# Rx.net
KiCad netlist of a schematic drawn in EAGLE
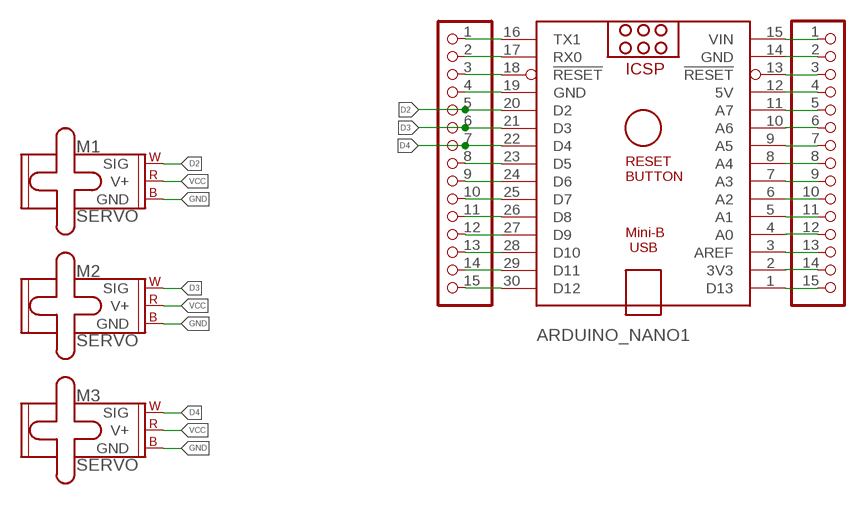
[diagram p0: schematic, sheet 1]

(export (version "E")
  (design (tool "Eeschema 10.0.6"))
  (components
    (comp (ref "ARDUINO_NANO1")
      (value "ARDUINO_NANO")
      (footprint "eagle-import:ARDUINO_NANO")
      (libsource (lib "eagle-import") (part "ARDUINO_NANO"))
    )
    (comp (ref "JP1")
      (value "PINHD-1X15-CB")
      (footprint "eagle-import:1X15-CB")
      (libsource (lib "eagle-import") (part "PINHD-1X15-CB"))
    )
    (comp (ref "JP2")
      (value "PINHD-1X15-CB")
      (footprint "eagle-import:1X15-CB")
      (libsource (lib "eagle-import") (part "PINHD-1X15-CB"))
    )
    (comp (ref "M1")
      (value "SERVO")
      (footprint "eagle-import:1X03")
      (libsource (lib "eagle-import") (part "SERVO"))
    )
    (comp (ref "M2")
      (value "SERVO")
      (footprint "eagle-import:1X03")
      (libsource (lib "eagle-import") (part "SERVO"))
    )
    (comp (ref "M3")
      (value "SERVO")
      (footprint "eagle-import:1X03")
      (libsource (lib "eagle-import") (part "SERVO"))
    )
  )
  (nets
    (net (code "1") (name "D2") (class "Default")
      (node (ref "ARDUINO_NANO1") (pin "20") (pinfunction "D2_20") (pintype "bidirectional"))
      (node (ref "JP2") (pin "5") (pinfunction "5_5") (pintype "passive"))
      (node (ref "M1") (pin "1") (pinfunction "SIG_1") (pintype "bidirectional"))
    )
    (net (code "2") (name "D3") (class "Default")
      (node (ref "ARDUINO_NANO1") (pin "21") (pinfunction "D3_21") (pintype "bidirectional"))
      (node (ref "JP2") (pin "6") (pinfunction "6_6") (pintype "passive"))
      (node (ref "M2") (pin "1") (pinfunction "SIG_1") (pintype "bidirectional"))
    )
    (net (code "3") (name "D4") (class "Default")
      (node (ref "ARDUINO_NANO1") (pin "22") (pinfunction "D4_22") (pintype "bidirectional"))
      (node (ref "JP2") (pin "7") (pinfunction "7_7") (pintype "passive"))
      (node (ref "M3") (pin "1") (pinfunction "SIG_1") (pintype "bidirectional"))
    )
    (net (code "4") (name "GND") (class "Default")
      (node (ref "M1") (pin "3") (pinfunction "GND_3") (pintype "bidirectional"))
      (node (ref "M2") (pin "3") (pinfunction "GND_3") (pintype "bidirectional"))
      (node (ref "M3") (pin "3") (pinfunction "GND_3") (pintype "bidirectional"))
    )
    (net (code "5") (name "Net-(ARDUINO_NANO1-3V3)") (class "Default")
      (node (ref "ARDUINO_NANO1") (pin "2") (pinfunction "3V3_2") (pintype "output"))
      (node (ref "JP1") (pin "14") (pinfunction "14_14") (pintype "passive"))
    )
    (net (code "6") (name "Net-(ARDUINO_NANO1-5V)") (class "Default")
      (node (ref "ARDUINO_NANO1") (pin "12") (pinfunction "5V_12") (pintype "power_in"))
      (node (ref "JP1") (pin "4") (pinfunction "4_4") (pintype "passive"))
    )
    (net (code "7") (name "Net-(ARDUINO_NANO1-A0)") (class "Default")
      (node (ref "ARDUINO_NANO1") (pin "4") (pinfunction "A0_4") (pintype "bidirectional"))
      (node (ref "JP1") (pin "12") (pinfunction "12_12") (pintype "passive"))
    )
    (net (code "8") (name "Net-(ARDUINO_NANO1-A1)") (class "Default")
      (node (ref "ARDUINO_NANO1") (pin "5") (pinfunction "A1_5") (pintype "bidirectional"))
      (node (ref "JP1") (pin "11") (pinfunction "11_11") (pintype "passive"))
    )
    (net (code "9") (name "Net-(ARDUINO_NANO1-A2)") (class "Default")
      (node (ref "ARDUINO_NANO1") (pin "6") (pinfunction "A2_6") (pintype "bidirectional"))
      (node (ref "JP1") (pin "10") (pinfunction "10_10") (pintype "passive"))
    )
    (net (code "10") (name "Net-(ARDUINO_NANO1-A3)") (class "Default")
      (node (ref "ARDUINO_NANO1") (pin "7") (pinfunction "A3_7") (pintype "bidirectional"))
      (node (ref "JP1") (pin "9") (pinfunction "9_9") (pintype "passive"))
    )
    (net (code "11") (name "Net-(ARDUINO_NANO1-A4)") (class "Default")
      (node (ref "ARDUINO_NANO1") (pin "8") (pinfunction "A4_8") (pintype "bidirectional"))
      (node (ref "JP1") (pin "8") (pinfunction "8_8") (pintype "passive"))
    )
    (net (code "12") (name "Net-(ARDUINO_NANO1-A5)") (class "Default")
      (node (ref "ARDUINO_NANO1") (pin "9") (pinfunction "A5_9") (pintype "bidirectional"))
      (node (ref "JP1") (pin "7") (pinfunction "7_7") (pintype "passive"))
    )
    (net (code "13") (name "Net-(ARDUINO_NANO1-A6)") (class "Default")
      (node (ref "ARDUINO_NANO1") (pin "10") (pinfunction "A6_10") (pintype "bidirectional"))
      (node (ref "JP1") (pin "6") (pinfunction "6_6") (pintype "passive"))
    )
    (net (code "14") (name "Net-(ARDUINO_NANO1-A7)") (class "Default")
      (node (ref "ARDUINO_NANO1") (pin "11") (pinfunction "A7_11") (pintype "bidirectional"))
      (node (ref "JP1") (pin "5") (pinfunction "5_5") (pintype "passive"))
    )
    (net (code "15") (name "Net-(ARDUINO_NANO1-AREF)") (class "Default")
      (node (ref "ARDUINO_NANO1") (pin "3") (pinfunction "AREF_3") (pintype "input"))
      (node (ref "JP1") (pin "13") (pinfunction "13_13") (pintype "passive"))
    )
    (net (code "16") (name "Net-(ARDUINO_NANO1-D5)") (class "Default")
      (node (ref "ARDUINO_NANO1") (pin "23") (pinfunction "D5_23") (pintype "bidirectional"))
      (node (ref "JP2") (pin "8") (pinfunction "8_8") (pintype "passive"))
    )
    (net (code "17") (name "Net-(ARDUINO_NANO1-D6)") (class "Default")
      (node (ref "ARDUINO_NANO1") (pin "24") (pinfunction "D6_24") (pintype "bidirectional"))
      (node (ref "JP2") (pin "9") (pinfunction "9_9") (pintype "passive"))
    )
    (net (code "18") (name "Net-(ARDUINO_NANO1-D7)") (class "Default")
      (node (ref "ARDUINO_NANO1") (pin "25") (pinfunction "D7_25") (pintype "bidirectional"))
      (node (ref "JP2") (pin "10") (pinfunction "10_10") (pintype "passive"))
    )
    (net (code "19") (name "Net-(ARDUINO_NANO1-D8)") (class "Default")
      (node (ref "ARDUINO_NANO1") (pin "26") (pinfunction "D8_26") (pintype "bidirectional"))
      (node (ref "JP2") (pin "11") (pinfunction "11_11") (pintype "passive"))
    )
    (net (code "20") (name "Net-(ARDUINO_NANO1-D9)") (class "Default")
      (node (ref "ARDUINO_NANO1") (pin "27") (pinfunction "D9_27") (pintype "bidirectional"))
      (node (ref "JP2") (pin "12") (pinfunction "12_12") (pintype "passive"))
    )
    (net (code "21") (name "Net-(ARDUINO_NANO1-D10)") (class "Default")
      (node (ref "ARDUINO_NANO1") (pin "28") (pinfunction "D10_28") (pintype "bidirectional"))
      (node (ref "JP2") (pin "13") (pinfunction "13_13") (pintype "passive"))
    )
    (net (code "22") (name "Net-(ARDUINO_NANO1-D11)") (class "Default")
      (node (ref "ARDUINO_NANO1") (pin "29") (pinfunction "D11_29") (pintype "bidirectional"))
      (node (ref "JP2") (pin "14") (pinfunction "14_14") (pintype "passive"))
    )
    (net (code "23") (name "Net-(ARDUINO_NANO1-D12)") (class "Default")
      (node (ref "ARDUINO_NANO1") (pin "30") (pinfunction "D12_30") (pintype "bidirectional"))
      (node (ref "JP2") (pin "15") (pinfunction "15_15") (pintype "passive"))
    )
    (net (code "24") (name "Net-(ARDUINO_NANO1-D13)") (class "Default")
      (node (ref "ARDUINO_NANO1") (pin "1") (pinfunction "D13_1") (pintype "bidirectional"))
      (node (ref "JP1") (pin "15") (pinfunction "15_15") (pintype "passive"))
    )
    (net (code "25") (name "Net-(ARDUINO_NANO1-GND-Pad14)") (class "Default")
      (node (ref "ARDUINO_NANO1") (pin "14") (pinfunction "GND_14") (pintype "power_in"))
      (node (ref "JP1") (pin "2") (pinfunction "2_2") (pintype "passive"))
    )
    (net (code "26") (name "Net-(ARDUINO_NANO1-GND-Pad19)") (class "Default")
      (node (ref "ARDUINO_NANO1") (pin "19") (pinfunction "GND_19") (pintype "power_in"))
      (node (ref "JP2") (pin "4") (pinfunction "4_4") (pintype "passive"))
    )
    (net (code "27") (name "Net-(ARDUINO_NANO1-RX0)") (class "Default")
      (node (ref "ARDUINO_NANO1") (pin "17") (pinfunction "RX0_17") (pintype "bidirectional"))
      (node (ref "JP2") (pin "2") (pinfunction "2_2") (pintype "passive"))
    )
    (net (code "28") (name "Net-(ARDUINO_NANO1-TX1)") (class "Default")
      (node (ref "ARDUINO_NANO1") (pin "16") (pinfunction "TX1_16") (pintype "bidirectional"))
      (node (ref "JP2") (pin "1") (pinfunction "1_1") (pintype "passive"))
    )
    (net (code "29") (name "Net-(ARDUINO_NANO1-VIN)") (class "Default")
      (node (ref "ARDUINO_NANO1") (pin "15") (pinfunction "VIN_15") (pintype "power_in"))
      (node (ref "JP1") (pin "1") (pinfunction "1_1") (pintype "passive"))
    )
    (net (code "30") (name "Net-(ARDUINO_NANO1-~{RESET}-Pad13)") (class "Default")
      (node (ref "ARDUINO_NANO1") (pin "13") (pinfunction "~{RESET}_13") (pintype "input"))
      (node (ref "JP1") (pin "3") (pinfunction "3_3") (pintype "passive"))
    )
    (net (code "31") (name "Net-(ARDUINO_NANO1-~{RESET}-Pad18)") (class "Default")
      (node (ref "ARDUINO_NANO1") (pin "18") (pinfunction "~{RESET}_18") (pintype "input"))
      (node (ref "JP2") (pin "3") (pinfunction "3_3") (pintype "passive"))
    )
    (net (code "32") (name "VCC") (class "Default")
      (node (ref "M1") (pin "2") (pinfunction "V+_2") (pintype "bidirectional"))
      (node (ref "M2") (pin "2") (pinfunction "V+_2") (pintype "bidirectional"))
      (node (ref "M3") (pin "2") (pinfunction "V+_2") (pintype "bidirectional"))
    )
  )
)
